# Schematics.net
KiCad netlist of a schematic drawn in EAGLE
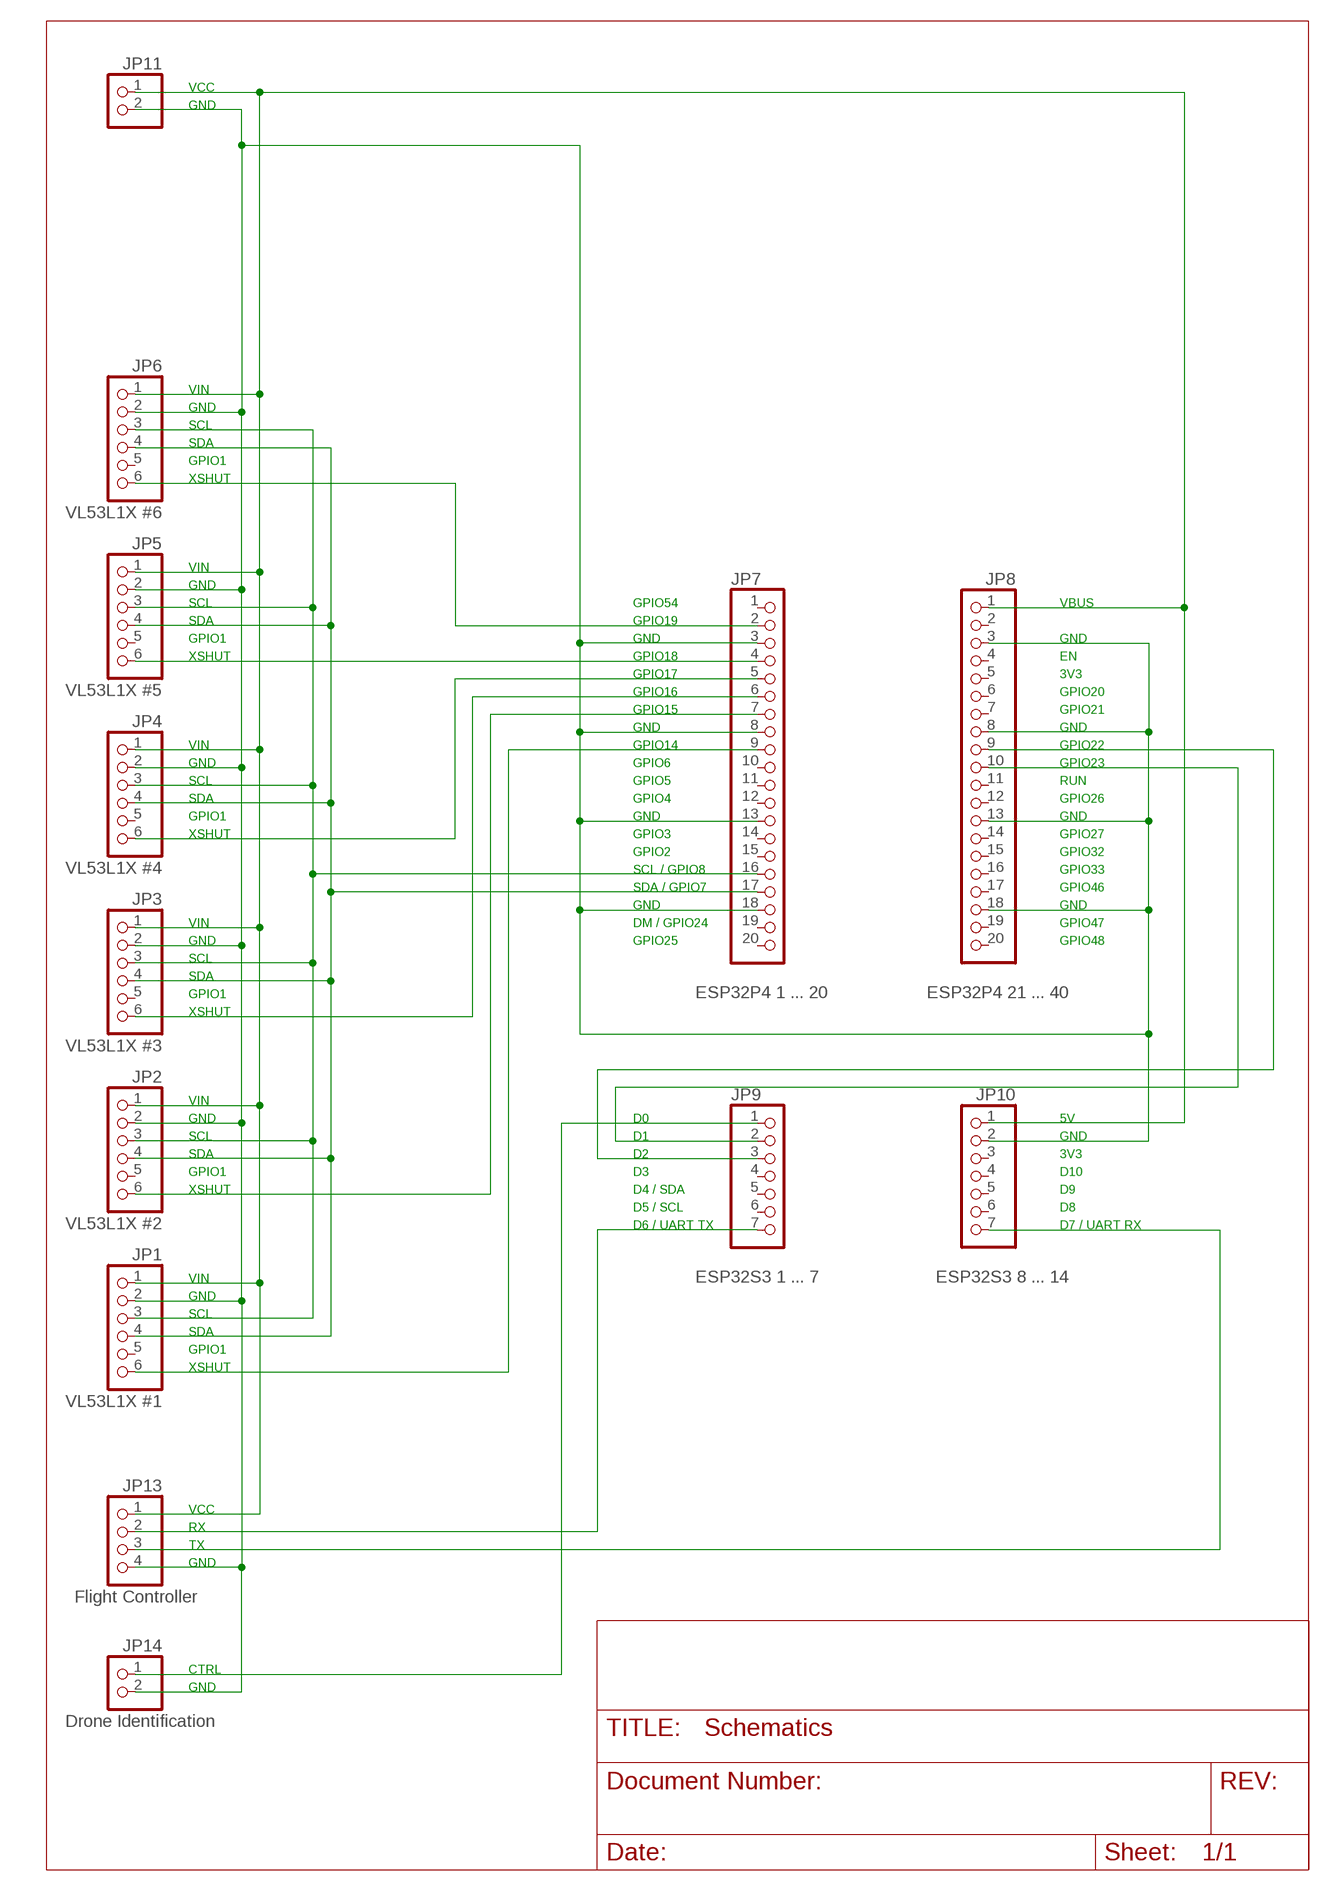
[diagram p0: schematic, sheet 1]

(export (version "E")
  (design (tool "Eeschema 10.0.6"))
  (components
    (comp (ref "JP1")
      (value "VL53L1X #1")
      (footprint "eagle-import:1X06")
      (libsource (lib "eagle-import") (part "PINHD-1X6"))
    )
    (comp (ref "JP2")
      (value "VL53L1X #2")
      (footprint "eagle-import:1X06")
      (libsource (lib "eagle-import") (part "PINHD-1X6"))
    )
    (comp (ref "JP3")
      (value "VL53L1X #3")
      (footprint "eagle-import:1X06")
      (libsource (lib "eagle-import") (part "PINHD-1X6"))
    )
    (comp (ref "JP4")
      (value "VL53L1X #4")
      (footprint "eagle-import:1X06")
      (libsource (lib "eagle-import") (part "PINHD-1X6"))
    )
    (comp (ref "JP5")
      (value "VL53L1X #5")
      (footprint "eagle-import:1X06")
      (libsource (lib "eagle-import") (part "PINHD-1X6"))
    )
    (comp (ref "JP6")
      (value "VL53L1X #6")
      (footprint "eagle-import:1X06")
      (libsource (lib "eagle-import") (part "PINHD-1X6"))
    )
    (comp (ref "JP7")
      (value "ESP32P4 1 ... 20")
      (footprint "eagle-import:1X20")
      (libsource (lib "eagle-import") (part "PINHD-1X20"))
    )
    (comp (ref "JP8")
      (value "ESP32P4 21 ... 40")
      (footprint "eagle-import:1X20")
      (libsource (lib "eagle-import") (part "PINHD-1X20"))
    )
    (comp (ref "JP9")
      (value "ESP32S3 1 ... 7")
      (footprint "eagle-import:1X07")
      (libsource (lib "eagle-import") (part "PINHD-1X7"))
    )
    (comp (ref "JP10")
      (value "ESP32S3 8 ... 14")
      (footprint "eagle-import:1X07")
      (libsource (lib "eagle-import") (part "PINHD-1X7"))
    )
    (comp (ref "JP11")
      (value "PINHD-1X2")
      (footprint "eagle-import:1X02")
      (libsource (lib "eagle-import") (part "PINHD-1X2"))
    )
    (comp (ref "JP13")
      (value "Flight Controller")
      (footprint "eagle-import:1X04")
      (libsource (lib "eagle-import") (part "PINHD-1X4"))
    )
    (comp (ref "JP14")
      (value "Drone Identification")
      (footprint "eagle-import:1X02")
      (libsource (lib "eagle-import") (part "PINHD-1X2"))
    )
  )
  (nets
    (net (code "1") (name "Net-(JP1-Pad1)") (class "Default")
      (node (ref "JP1") (pin "1") (pinfunction "1_1") (pintype "passive"))
      (node (ref "JP10") (pin "1") (pinfunction "1_1") (pintype "passive"))
      (node (ref "JP11") (pin "1") (pinfunction "1_1") (pintype "passive"))
      (node (ref "JP13") (pin "1") (pinfunction "1_1") (pintype "passive"))
      (node (ref "JP2") (pin "1") (pinfunction "1_1") (pintype "passive"))
      (node (ref "JP3") (pin "1") (pinfunction "1_1") (pintype "passive"))
      (node (ref "JP4") (pin "1") (pinfunction "1_1") (pintype "passive"))
      (node (ref "JP5") (pin "1") (pinfunction "1_1") (pintype "passive"))
      (node (ref "JP6") (pin "1") (pinfunction "1_1") (pintype "passive"))
      (node (ref "JP8") (pin "1") (pinfunction "1_1") (pintype "passive"))
    )
    (net (code "2") (name "Net-(JP1-Pad2)") (class "Default")
      (node (ref "JP1") (pin "2") (pinfunction "2_2") (pintype "passive"))
      (node (ref "JP10") (pin "2") (pinfunction "2_2") (pintype "passive"))
      (node (ref "JP11") (pin "2") (pinfunction "2_2") (pintype "passive"))
      (node (ref "JP13") (pin "4") (pinfunction "4_4") (pintype "passive"))
      (node (ref "JP14") (pin "2") (pinfunction "2_2") (pintype "passive"))
      (node (ref "JP2") (pin "2") (pinfunction "2_2") (pintype "passive"))
      (node (ref "JP3") (pin "2") (pinfunction "2_2") (pintype "passive"))
      (node (ref "JP4") (pin "2") (pinfunction "2_2") (pintype "passive"))
      (node (ref "JP5") (pin "2") (pinfunction "2_2") (pintype "passive"))
      (node (ref "JP6") (pin "2") (pinfunction "2_2") (pintype "passive"))
      (node (ref "JP7") (pin "13") (pinfunction "13_13") (pintype "passive"))
      (node (ref "JP7") (pin "18") (pinfunction "18_18") (pintype "passive"))
      (node (ref "JP7") (pin "3") (pinfunction "3_3") (pintype "passive"))
      (node (ref "JP7") (pin "8") (pinfunction "8_8") (pintype "passive"))
      (node (ref "JP8") (pin "13") (pinfunction "13_13") (pintype "passive"))
      (node (ref "JP8") (pin "18") (pinfunction "18_18") (pintype "passive"))
      (node (ref "JP8") (pin "3") (pinfunction "3_3") (pintype "passive"))
      (node (ref "JP8") (pin "8") (pinfunction "8_8") (pintype "passive"))
    )
    (net (code "3") (name "Net-(JP1-Pad3)") (class "Default")
      (node (ref "JP1") (pin "3") (pinfunction "3_3") (pintype "passive"))
      (node (ref "JP2") (pin "3") (pinfunction "3_3") (pintype "passive"))
      (node (ref "JP3") (pin "3") (pinfunction "3_3") (pintype "passive"))
      (node (ref "JP4") (pin "3") (pinfunction "3_3") (pintype "passive"))
      (node (ref "JP5") (pin "3") (pinfunction "3_3") (pintype "passive"))
      (node (ref "JP6") (pin "3") (pinfunction "3_3") (pintype "passive"))
      (node (ref "JP7") (pin "16") (pinfunction "16_16") (pintype "passive"))
    )
    (net (code "4") (name "Net-(JP1-Pad4)") (class "Default")
      (node (ref "JP1") (pin "4") (pinfunction "4_4") (pintype "passive"))
      (node (ref "JP2") (pin "4") (pinfunction "4_4") (pintype "passive"))
      (node (ref "JP3") (pin "4") (pinfunction "4_4") (pintype "passive"))
      (node (ref "JP4") (pin "4") (pinfunction "4_4") (pintype "passive"))
      (node (ref "JP5") (pin "4") (pinfunction "4_4") (pintype "passive"))
      (node (ref "JP6") (pin "4") (pinfunction "4_4") (pintype "passive"))
      (node (ref "JP7") (pin "17") (pinfunction "17_17") (pintype "passive"))
    )
    (net (code "5") (name "Net-(JP1-Pad6)") (class "Default")
      (node (ref "JP1") (pin "6") (pinfunction "6_6") (pintype "passive"))
      (node (ref "JP7") (pin "9") (pinfunction "9_9") (pintype "passive"))
    )
    (net (code "6") (name "Net-(JP2-Pad6)") (class "Default")
      (node (ref "JP2") (pin "6") (pinfunction "6_6") (pintype "passive"))
      (node (ref "JP7") (pin "7") (pinfunction "7_7") (pintype "passive"))
    )
    (net (code "7") (name "Net-(JP3-Pad6)") (class "Default")
      (node (ref "JP3") (pin "6") (pinfunction "6_6") (pintype "passive"))
      (node (ref "JP7") (pin "6") (pinfunction "6_6") (pintype "passive"))
    )
    (net (code "8") (name "Net-(JP4-Pad6)") (class "Default")
      (node (ref "JP4") (pin "6") (pinfunction "6_6") (pintype "passive"))
      (node (ref "JP7") (pin "5") (pinfunction "5_5") (pintype "passive"))
    )
    (net (code "9") (name "Net-(JP5-Pad6)") (class "Default")
      (node (ref "JP5") (pin "6") (pinfunction "6_6") (pintype "passive"))
      (node (ref "JP7") (pin "4") (pinfunction "4_4") (pintype "passive"))
    )
    (net (code "10") (name "Net-(JP6-Pad6)") (class "Default")
      (node (ref "JP6") (pin "6") (pinfunction "6_6") (pintype "passive"))
      (node (ref "JP7") (pin "2") (pinfunction "2_2") (pintype "passive"))
    )
    (net (code "11") (name "Net-(JP8-Pad9)") (class "Default")
      (node (ref "JP8") (pin "9") (pinfunction "9_9") (pintype "passive"))
      (node (ref "JP9") (pin "3") (pinfunction "3_3") (pintype "passive"))
    )
    (net (code "12") (name "Net-(JP8-Pad10)") (class "Default")
      (node (ref "JP8") (pin "10") (pinfunction "10_10") (pintype "passive"))
      (node (ref "JP9") (pin "2") (pinfunction "2_2") (pintype "passive"))
    )
    (net (code "13") (name "Net-(JP10-Pad7)") (class "Default")
      (node (ref "JP10") (pin "7") (pinfunction "7_7") (pintype "passive"))
      (node (ref "JP13") (pin "3") (pinfunction "3_3") (pintype "passive"))
    )
    (net (code "14") (name "Net-(JP13-Pad2)") (class "Default")
      (node (ref "JP13") (pin "2") (pinfunction "2_2") (pintype "passive"))
      (node (ref "JP9") (pin "7") (pinfunction "7_7") (pintype "passive"))
    )
    (net (code "15") (name "Net-(JP14-Pad1)") (class "Default")
      (node (ref "JP14") (pin "1") (pinfunction "1_1") (pintype "passive"))
      (node (ref "JP9") (pin "1") (pinfunction "1_1") (pintype "passive"))
    )
    (net (code "16") (name "unconnected-(JP1-Pad5)") (class "Default")
      (node (ref "JP1") (pin "5") (pinfunction "5_5") (pintype "passive"))
    )
    (net (code "17") (name "unconnected-(JP2-Pad5)") (class "Default")
      (node (ref "JP2") (pin "5") (pinfunction "5_5") (pintype "passive"))
    )
    (net (code "18") (name "unconnected-(JP3-Pad5)") (class "Default")
      (node (ref "JP3") (pin "5") (pinfunction "5_5") (pintype "passive"))
    )
    (net (code "19") (name "unconnected-(JP4-Pad5)") (class "Default")
      (node (ref "JP4") (pin "5") (pinfunction "5_5") (pintype "passive"))
    )
    (net (code "20") (name "unconnected-(JP5-Pad5)") (class "Default")
      (node (ref "JP5") (pin "5") (pinfunction "5_5") (pintype "passive"))
    )
    (net (code "21") (name "unconnected-(JP6-Pad5)") (class "Default")
      (node (ref "JP6") (pin "5") (pinfunction "5_5") (pintype "passive"))
    )
    (net (code "22") (name "unconnected-(JP7-Pad1)") (class "Default")
      (node (ref "JP7") (pin "1") (pinfunction "1_1") (pintype "passive"))
    )
    (net (code "23") (name "unconnected-(JP7-Pad10)") (class "Default")
      (node (ref "JP7") (pin "10") (pinfunction "10_10") (pintype "passive"))
    )
    (net (code "24") (name "unconnected-(JP7-Pad11)") (class "Default")
      (node (ref "JP7") (pin "11") (pinfunction "11_11") (pintype "passive"))
    )
    (net (code "25") (name "unconnected-(JP7-Pad12)") (class "Default")
      (node (ref "JP7") (pin "12") (pinfunction "12_12") (pintype "passive"))
    )
    (net (code "26") (name "unconnected-(JP7-Pad14)") (class "Default")
      (node (ref "JP7") (pin "14") (pinfunction "14_14") (pintype "passive"))
    )
    (net (code "27") (name "unconnected-(JP7-Pad15)") (class "Default")
      (node (ref "JP7") (pin "15") (pinfunction "15_15") (pintype "passive"))
    )
    (net (code "28") (name "unconnected-(JP7-Pad19)") (class "Default")
      (node (ref "JP7") (pin "19") (pinfunction "19_19") (pintype "passive"))
    )
    (net (code "29") (name "unconnected-(JP7-Pad20)") (class "Default")
      (node (ref "JP7") (pin "20") (pinfunction "20_20") (pintype "passive"))
    )
    (net (code "30") (name "unconnected-(JP8-Pad2)") (class "Default")
      (node (ref "JP8") (pin "2") (pinfunction "2_2") (pintype "passive"))
    )
    (net (code "31") (name "unconnected-(JP8-Pad4)") (class "Default")
      (node (ref "JP8") (pin "4") (pinfunction "4_4") (pintype "passive"))
    )
    (net (code "32") (name "unconnected-(JP8-Pad5)") (class "Default")
      (node (ref "JP8") (pin "5") (pinfunction "5_5") (pintype "passive"))
    )
    (net (code "33") (name "unconnected-(JP8-Pad6)") (class "Default")
      (node (ref "JP8") (pin "6") (pinfunction "6_6") (pintype "passive"))
    )
    (net (code "34") (name "unconnected-(JP8-Pad7)") (class "Default")
      (node (ref "JP8") (pin "7") (pinfunction "7_7") (pintype "passive"))
    )
    (net (code "35") (name "unconnected-(JP8-Pad11)") (class "Default")
      (node (ref "JP8") (pin "11") (pinfunction "11_11") (pintype "passive"))
    )
    (net (code "36") (name "unconnected-(JP8-Pad12)") (class "Default")
      (node (ref "JP8") (pin "12") (pinfunction "12_12") (pintype "passive"))
    )
    (net (code "37") (name "unconnected-(JP8-Pad14)") (class "Default")
      (node (ref "JP8") (pin "14") (pinfunction "14_14") (pintype "passive"))
    )
    (net (code "38") (name "unconnected-(JP8-Pad15)") (class "Default")
      (node (ref "JP8") (pin "15") (pinfunction "15_15") (pintype "passive"))
    )
    (net (code "39") (name "unconnected-(JP8-Pad16)") (class "Default")
      (node (ref "JP8") (pin "16") (pinfunction "16_16") (pintype "passive"))
    )
    (net (code "40") (name "unconnected-(JP8-Pad17)") (class "Default")
      (node (ref "JP8") (pin "17") (pinfunction "17_17") (pintype "passive"))
    )
    (net (code "41") (name "unconnected-(JP8-Pad19)") (class "Default")
      (node (ref "JP8") (pin "19") (pinfunction "19_19") (pintype "passive"))
    )
    (net (code "42") (name "unconnected-(JP8-Pad20)") (class "Default")
      (node (ref "JP8") (pin "20") (pinfunction "20_20") (pintype "passive"))
    )
    (net (code "43") (name "unconnected-(JP9-Pad4)") (class "Default")
      (node (ref "JP9") (pin "4") (pinfunction "4_4") (pintype "passive"))
    )
    (net (code "44") (name "unconnected-(JP9-Pad5)") (class "Default")
      (node (ref "JP9") (pin "5") (pinfunction "5_5") (pintype "passive"))
    )
    (net (code "45") (name "unconnected-(JP9-Pad6)") (class "Default")
      (node (ref "JP9") (pin "6") (pinfunction "6_6") (pintype "passive"))
    )
    (net (code "46") (name "unconnected-(JP10-Pad3)") (class "Default")
      (node (ref "JP10") (pin "3") (pinfunction "3_3") (pintype "passive"))
    )
    (net (code "47") (name "unconnected-(JP10-Pad4)") (class "Default")
      (node (ref "JP10") (pin "4") (pinfunction "4_4") (pintype "passive"))
    )
    (net (code "48") (name "unconnected-(JP10-Pad5)") (class "Default")
      (node (ref "JP10") (pin "5") (pinfunction "5_5") (pintype "passive"))
    )
    (net (code "49") (name "unconnected-(JP10-Pad6)") (class "Default")
      (node (ref "JP10") (pin "6") (pinfunction "6_6") (pintype "passive"))
    )
  )
)
